# logicboard.net
KiCad netlist of a schematic drawn in EAGLE
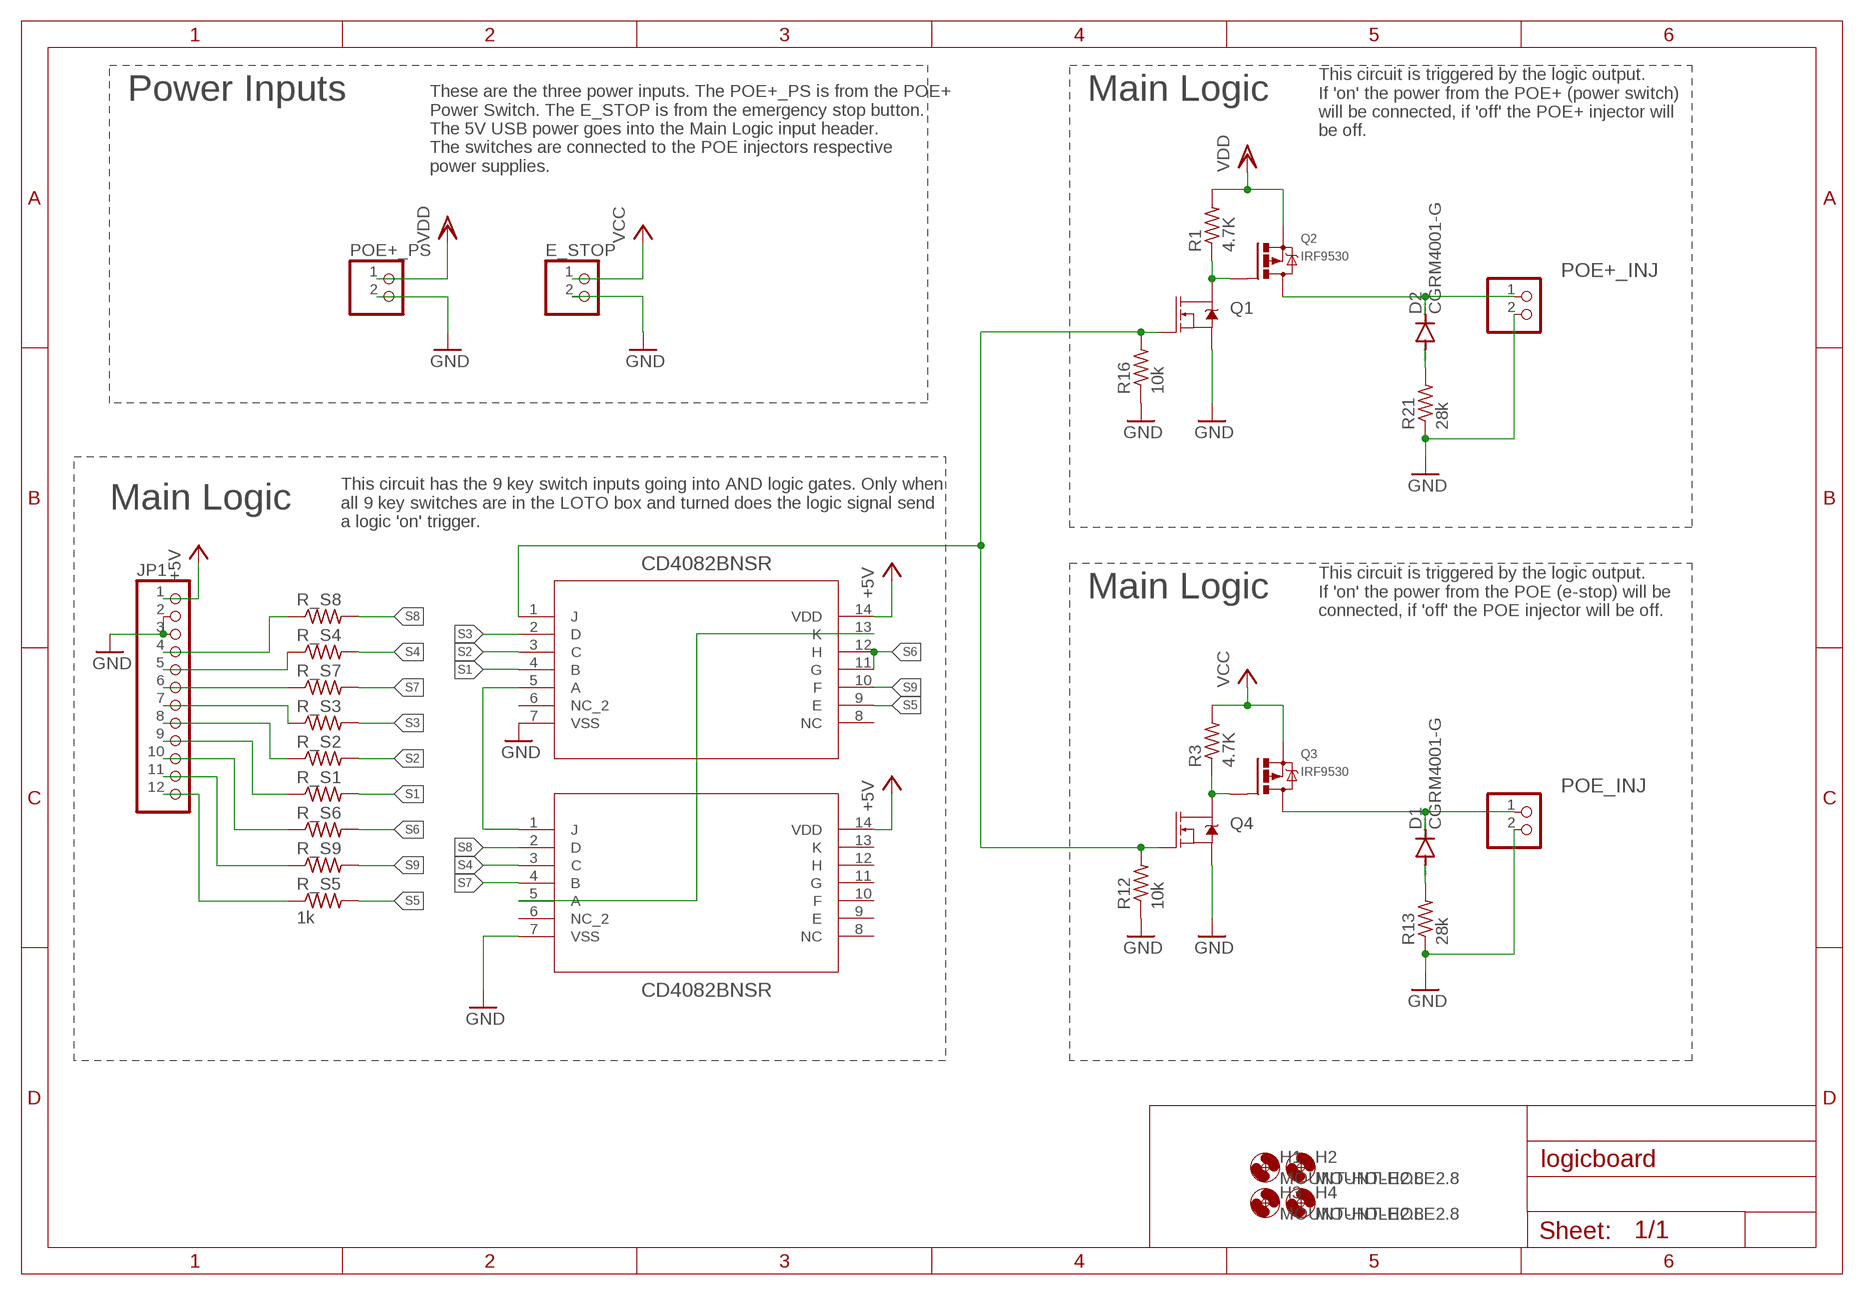
[diagram p0: schematic, sheet 1]

(export (version "E")
  (design (tool "Eeschema 10.0.6"))
  (components
    (comp (ref "D1")
      (value "CGRM4001-G")
      (footprint "eagle-import:SOD-123_MINI-SMA")
      (fields (field (name "MFR") "Central Semiconductor Corp") (field (name "MPN") "CMHSH5-4 TR PBFREE"))
      (libsource (lib "eagle-import") (part "CGRM400-G1"))
    )
    (comp (ref "D2")
      (value "CGRM4001-G")
      (footprint "eagle-import:SOD-123_MINI-SMA")
      (fields (field (name "MFR") "Central Semiconductor Corp") (field (name "MPN") "CMHSH5-4 TR PBFREE"))
      (libsource (lib "eagle-import") (part "CGRM400-G1"))
    )
    (comp (ref "E_STOP")
      (value "PINHD-1X2")
      (footprint "eagle-import:1X02")
      (fields (field (name "MFR") "On Shore Technology Inc.") (field (name "MPN") "OSTVN02A150"))
      (libsource (lib "eagle-import") (part "PINHD-1X2"))
    )
    (comp (ref "H1")
      (value "MOUNT-HOLE2.8")
      (footprint "eagle-import:2,8")
      (libsource (lib "eagle-import") (part "MOUNT-HOLE2.8"))
    )
    (comp (ref "H2")
      (value "MOUNT-HOLE2.8")
      (footprint "eagle-import:2,8")
      (libsource (lib "eagle-import") (part "MOUNT-HOLE2.8"))
    )
    (comp (ref "H3")
      (value "MOUNT-HOLE2.8")
      (footprint "eagle-import:2,8")
      (libsource (lib "eagle-import") (part "MOUNT-HOLE2.8"))
    )
    (comp (ref "H4")
      (value "MOUNT-HOLE2.8")
      (footprint "eagle-import:2,8")
      (libsource (lib "eagle-import") (part "MOUNT-HOLE2.8"))
    )
    (comp (ref "JP1")
      (value "PINHD-1X12")
      (footprint "eagle-import:1X12")
      (fields (field (name "MFR") "TE Connectivity AMP Connectors") (field (name "MPN") "1-640454-2"))
      (libsource (lib "eagle-import") (part "PINHD-1X12"))
    )
    (comp (ref "POE+_INJ")
      (value "PINHD-1X2")
      (footprint "eagle-import:1X02")
      (fields (field (name "MFR") "Molex") (field (name "MPN") "0022232021"))
      (libsource (lib "eagle-import") (part "PINHD-1X2"))
    )
    (comp (ref "POE+_PS")
      (value "PINHD-1X2")
      (footprint "eagle-import:1X02")
      (fields (field (name "MFR") "On Shore Technology Inc.") (field (name "MPN") "OSTVN02A150"))
      (libsource (lib "eagle-import") (part "PINHD-1X2"))
    )
    (comp (ref "POE_INJ")
      (value "PINHD-1X2")
      (footprint "eagle-import:1X02")
      (fields (field (name "MFR") "Molex") (field (name "MPN") "0022232021"))
      (libsource (lib "eagle-import") (part "PINHD-1X2"))
    )
    (comp (ref "Q1")
      (value "220mA/50V/3.5Ω")
      (footprint "eagle-import:SOT23-3")
      (fields (field (name "MFR") "Nexperia USA Inc.") (field (name "MPN") "BSS138P,215"))
      (libsource (lib "eagle-import") (part "MOSFET-NCH-BSS138"))
    )
    (comp (ref "Q2")
      (value "IRF9530")
      (footprint "eagle-import:TO220BV")
      (fields (field (name "MFR") "Infineon Technologies") (field (name "MPN") "IRF9530NPBF"))
      (libsource (lib "eagle-import") (part "IRF9530"))
    )
    (comp (ref "Q3")
      (value "IRF9530")
      (footprint "eagle-import:TO220BV")
      (fields (field (name "MFR") "Infineon Technologies") (field (name "MPN") "IRF9530NPBF"))
      (libsource (lib "eagle-import") (part "IRF9530"))
    )
    (comp (ref "Q4")
      (value "220mA/50V/3.5Ω")
      (footprint "eagle-import:SOT23-3")
      (fields (field (name "MFR") "Nexperia USA Inc.") (field (name "MPN") "BSS138P,215"))
      (libsource (lib "eagle-import") (part "MOSFET-NCH-BSS138"))
    )
    (comp (ref "R1")
      (value "4.7K")
      (footprint "eagle-import:.0805-C-NOSILK")
      (fields (field (name "MFR") "Yageo") (field (name "MPN") "RC0805FR-074K7L"))
      (libsource (lib "eagle-import") (part "R-US_0805-C-NOSILK"))
    )
    (comp (ref "R3")
      (value "4.7K")
      (footprint "eagle-import:.0805-C-NOSILK")
      (fields (field (name "MFR") "Yageo") (field (name "MPN") "RC0805FR-074K7L"))
      (libsource (lib "eagle-import") (part "R-US_0805-C-NOSILK"))
    )
    (comp (ref "R12")
      (value "10k")
      (footprint "eagle-import:.0805-C-NOSILK")
      (fields (field (name "MFR") "Yageo") (field (name "MPN") "RC0805FR-0710KL"))
      (libsource (lib "eagle-import") (part "R-US_0805-C-NOSILK"))
    )
    (comp (ref "R13")
      (value "28k")
      (footprint "eagle-import:.0805-C-NOSILK")
      (fields (field (name "MFR") "Stackpole Electronics Inc") (field (name "MPN") "RMCF0805FT28K0"))
      (libsource (lib "eagle-import") (part "R-US_0805-C-NOSILK"))
    )
    (comp (ref "R16")
      (value "10k")
      (footprint "eagle-import:.0805-C-NOSILK")
      (fields (field (name "MFR") "Yageo") (field (name "MPN") "RC0805FR-0710KL"))
      (libsource (lib "eagle-import") (part "R-US_0805-C-NOSILK"))
    )
    (comp (ref "R21")
      (value "28k")
      (footprint "eagle-import:.0805-C-NOSILK")
      (fields (field (name "MFR") "Stackpole Electronics Inc") (field (name "MPN") "RMCF0805FT28K0"))
      (libsource (lib "eagle-import") (part "R-US_0805-C-NOSILK"))
    )
    (comp (ref "R_S1")
      (value "1k")
      (footprint "eagle-import:.0603-C-NOSILK")
      (fields (field (name "MFR") "Panasonic Electronic Components") (field (name "MPN") "ERJ-PA3F1001V"))
      (libsource (lib "eagle-import") (part "R-US_0603-C-NOSILK"))
    )
    (comp (ref "R_S2")
      (value "1k")
      (footprint "eagle-import:.0603-C-NOSILK")
      (fields (field (name "MFR") "Panasonic Electronic Components") (field (name "MPN") "ERJ-PA3F1001V"))
      (libsource (lib "eagle-import") (part "R-US_0603-C-NOSILK"))
    )
    (comp (ref "R_S3")
      (value "1k")
      (footprint "eagle-import:.0603-C-NOSILK")
      (fields (field (name "MFR") "Panasonic Electronic Components") (field (name "MPN") "ERJ-PA3F1001V"))
      (libsource (lib "eagle-import") (part "R-US_0603-C-NOSILK"))
    )
    (comp (ref "R_S4")
      (value "1k")
      (footprint "eagle-import:.0603-C-NOSILK")
      (fields (field (name "MFR") "Panasonic Electronic Components") (field (name "MPN") "ERJ-PA3F1001V"))
      (libsource (lib "eagle-import") (part "R-US_0603-C-NOSILK"))
    )
    (comp (ref "R_S5")
      (value "1k")
      (footprint "eagle-import:.0603-C-NOSILK")
      (fields (field (name "MFR") "Panasonic Electronic Components") (field (name "MPN") "ERJ-PA3F1001V"))
      (libsource (lib "eagle-import") (part "R-US_0603-C-NOSILK"))
    )
    (comp (ref "R_S6")
      (value "1k")
      (footprint "eagle-import:.0603-C-NOSILK")
      (fields (field (name "MFR") "Panasonic Electronic Components") (field (name "MPN") "ERJ-PA3F1001V"))
      (libsource (lib "eagle-import") (part "R-US_0603-C-NOSILK"))
    )
    (comp (ref "R_S7")
      (value "1k")
      (footprint "eagle-import:.0603-C-NOSILK")
      (fields (field (name "MFR") "Panasonic Electronic Components") (field (name "MPN") "ERJ-PA3F1001V"))
      (libsource (lib "eagle-import") (part "R-US_0603-C-NOSILK"))
    )
    (comp (ref "R_S8")
      (value "1k")
      (footprint "eagle-import:.0603-C-NOSILK")
      (fields (field (name "MFR") "Panasonic Electronic Components") (field (name "MPN") "ERJ-PA3F1001V"))
      (libsource (lib "eagle-import") (part "R-US_0603-C-NOSILK"))
    )
    (comp (ref "R_S9")
      (value "1k")
      (footprint "eagle-import:.0603-C-NOSILK")
      (fields (field (name "MFR") "Panasonic Electronic Components") (field (name "MPN") "ERJ-PA3F1001V"))
      (libsource (lib "eagle-import") (part "R-US_0603-C-NOSILK"))
    )
    (comp (ref "U1")
      (value "CD4082BNSR")
      (footprint "eagle-import:NS14")
      (fields
        (field (name "GENERIC_PART_NUMBER") "CD4082B")
        (field (name "MANUFACTURER") "Texas Instruments")
      )
      (libsource (lib "eagle-import") (part "CD4082BNSR"))
    )
    (comp (ref "U2")
      (value "CD4082BNSR")
      (footprint "eagle-import:NS14")
      (fields
        (field (name "GENERIC_PART_NUMBER") "CD4082B")
        (field (name "MANUFACTURER") "Texas Instruments")
      )
      (libsource (lib "eagle-import") (part "CD4082BNSR"))
    )
  )
  (nets
    (net (code "1") (name "+5V") (class "Default")
      (node (ref "JP1") (pin "1") (pinfunction "1_1") (pintype "passive"))
      (node (ref "U1") (pin "14") (pinfunction "VDD_14") (pintype "power_in"))
      (node (ref "U2") (pin "14") (pinfunction "VDD_14") (pintype "power_in"))
    )
    (net (code "2") (name "GND") (class "Default")
      (node (ref "E_STOP") (pin "2") (pinfunction "2_2") (pintype "passive"))
      (node (ref "JP1") (pin "2") (pinfunction "2_2") (pintype "passive"))
      (node (ref "JP1") (pin "3") (pinfunction "3_3") (pintype "passive"))
      (node (ref "POE+_INJ") (pin "2") (pinfunction "2_2") (pintype "passive"))
      (node (ref "POE+_PS") (pin "2") (pinfunction "2_2") (pintype "passive"))
      (node (ref "POE_INJ") (pin "2") (pinfunction "2_2") (pintype "passive"))
      (node (ref "Q1") (pin "2") (pinfunction "S_2") (pintype "bidirectional"))
      (node (ref "Q4") (pin "2") (pinfunction "S_2") (pintype "bidirectional"))
      (node (ref "R12") (pin "1") (pinfunction "1_1") (pintype "passive"))
      (node (ref "R13") (pin "1") (pinfunction "1_1") (pintype "passive"))
      (node (ref "R16") (pin "1") (pinfunction "1_1") (pintype "passive"))
      (node (ref "R21") (pin "1") (pinfunction "1_1") (pintype "passive"))
      (node (ref "U1") (pin "7") (pinfunction "VSS_7") (pintype "power_in"))
      (node (ref "U2") (pin "7") (pinfunction "VSS_7") (pintype "power_in"))
    )
    (net (code "3") (name "Net-(D1-PadA)") (class "Default")
      (node (ref "D1") (pin "A") (pinfunction "A_A") (pintype "passive"))
      (node (ref "R13") (pin "2") (pinfunction "2_2") (pintype "passive"))
    )
    (net (code "4") (name "Net-(D1-PadC)") (class "Default")
      (node (ref "D1") (pin "C") (pinfunction "C_C") (pintype "passive"))
      (node (ref "POE_INJ") (pin "1") (pinfunction "1_1") (pintype "passive"))
      (node (ref "Q3") (pin "D") (pinfunction "D_D") (pintype "passive"))
    )
    (net (code "5") (name "Net-(D2-PadA)") (class "Default")
      (node (ref "D2") (pin "A") (pinfunction "A_A") (pintype "passive"))
      (node (ref "R21") (pin "2") (pinfunction "2_2") (pintype "passive"))
    )
    (net (code "6") (name "Net-(D2-PadC)") (class "Default")
      (node (ref "D2") (pin "C") (pinfunction "C_C") (pintype "passive"))
      (node (ref "POE+_INJ") (pin "1") (pinfunction "1_1") (pintype "passive"))
      (node (ref "Q2") (pin "D") (pinfunction "D_D") (pintype "passive"))
    )
    (net (code "7") (name "Net-(JP1-Pad4)") (class "Default")
      (node (ref "JP1") (pin "4") (pinfunction "4_4") (pintype "passive"))
      (node (ref "R_S8") (pin "1") (pinfunction "1_1") (pintype "passive"))
    )
    (net (code "8") (name "Net-(JP1-Pad5)") (class "Default")
      (node (ref "JP1") (pin "5") (pinfunction "5_5") (pintype "passive"))
      (node (ref "R_S4") (pin "1") (pinfunction "1_1") (pintype "passive"))
    )
    (net (code "9") (name "Net-(JP1-Pad6)") (class "Default")
      (node (ref "JP1") (pin "6") (pinfunction "6_6") (pintype "passive"))
      (node (ref "R_S7") (pin "1") (pinfunction "1_1") (pintype "passive"))
    )
    (net (code "10") (name "Net-(JP1-Pad7)") (class "Default")
      (node (ref "JP1") (pin "7") (pinfunction "7_7") (pintype "passive"))
      (node (ref "R_S3") (pin "1") (pinfunction "1_1") (pintype "passive"))
    )
    (net (code "11") (name "Net-(JP1-Pad8)") (class "Default")
      (node (ref "JP1") (pin "8") (pinfunction "8_8") (pintype "passive"))
      (node (ref "R_S2") (pin "1") (pinfunction "1_1") (pintype "passive"))
    )
    (net (code "12") (name "Net-(JP1-Pad9)") (class "Default")
      (node (ref "JP1") (pin "9") (pinfunction "9_9") (pintype "passive"))
      (node (ref "R_S1") (pin "1") (pinfunction "1_1") (pintype "passive"))
    )
    (net (code "13") (name "Net-(JP1-Pad10)") (class "Default")
      (node (ref "JP1") (pin "10") (pinfunction "10_10") (pintype "passive"))
      (node (ref "R_S6") (pin "1") (pinfunction "1_1") (pintype "passive"))
    )
    (net (code "14") (name "Net-(JP1-Pad11)") (class "Default")
      (node (ref "JP1") (pin "11") (pinfunction "11_11") (pintype "passive"))
      (node (ref "R_S9") (pin "1") (pinfunction "1_1") (pintype "passive"))
    )
    (net (code "15") (name "Net-(JP1-Pad12)") (class "Default")
      (node (ref "JP1") (pin "12") (pinfunction "12_12") (pintype "passive"))
      (node (ref "R_S5") (pin "1") (pinfunction "1_1") (pintype "passive"))
    )
    (net (code "16") (name "Net-(Q1-D)") (class "Default")
      (node (ref "Q1") (pin "3") (pinfunction "D_3") (pintype "bidirectional"))
      (node (ref "Q2") (pin "G") (pinfunction "G_G") (pintype "passive"))
      (node (ref "R1") (pin "1") (pinfunction "1_1") (pintype "passive"))
    )
    (net (code "17") (name "Net-(Q1-G)") (class "Default")
      (node (ref "Q1") (pin "1") (pinfunction "G_1") (pintype "bidirectional"))
      (node (ref "Q4") (pin "1") (pinfunction "G_1") (pintype "bidirectional"))
      (node (ref "R12") (pin "2") (pinfunction "2_2") (pintype "passive"))
      (node (ref "R16") (pin "2") (pinfunction "2_2") (pintype "passive"))
      (node (ref "U1") (pin "1") (pinfunction "J_1") (pintype "passive"))
    )
    (net (code "18") (name "Net-(Q4-D)") (class "Default")
      (node (ref "Q3") (pin "G") (pinfunction "G_G") (pintype "passive"))
      (node (ref "Q4") (pin "3") (pinfunction "D_3") (pintype "bidirectional"))
      (node (ref "R3") (pin "1") (pinfunction "1_1") (pintype "passive"))
    )
    (net (code "19") (name "Net-(U1-A)") (class "Default")
      (node (ref "U1") (pin "5") (pinfunction "A_5") (pintype "passive"))
      (node (ref "U2") (pin "1") (pinfunction "J_1") (pintype "passive"))
    )
    (net (code "20") (name "Net-(U1-K)") (class "Default")
      (node (ref "U1") (pin "13") (pinfunction "K_13") (pintype "passive"))
      (node (ref "U2") (pin "5") (pinfunction "A_5") (pintype "passive"))
    )
    (net (code "21") (name "S1") (class "Default")
      (node (ref "R_S1") (pin "2") (pinfunction "2_2") (pintype "passive"))
      (node (ref "U1") (pin "4") (pinfunction "B_4") (pintype "passive"))
    )
    (net (code "22") (name "S2") (class "Default")
      (node (ref "R_S2") (pin "2") (pinfunction "2_2") (pintype "passive"))
      (node (ref "U1") (pin "3") (pinfunction "C_3") (pintype "passive"))
    )
    (net (code "23") (name "S3") (class "Default")
      (node (ref "R_S3") (pin "2") (pinfunction "2_2") (pintype "passive"))
      (node (ref "U1") (pin "2") (pinfunction "D_2") (pintype "passive"))
    )
    (net (code "24") (name "S4") (class "Default")
      (node (ref "R_S4") (pin "2") (pinfunction "2_2") (pintype "passive"))
      (node (ref "U2") (pin "3") (pinfunction "C_3") (pintype "passive"))
    )
    (net (code "25") (name "S5") (class "Default")
      (node (ref "R_S5") (pin "2") (pinfunction "2_2") (pintype "passive"))
      (node (ref "U1") (pin "9") (pinfunction "E_9") (pintype "passive"))
    )
    (net (code "26") (name "S6") (class "Default")
      (node (ref "R_S6") (pin "2") (pinfunction "2_2") (pintype "passive"))
      (node (ref "U1") (pin "11") (pinfunction "G_11") (pintype "passive"))
      (node (ref "U1") (pin "12") (pinfunction "H_12") (pintype "passive"))
    )
    (net (code "27") (name "S7") (class "Default")
      (node (ref "R_S7") (pin "2") (pinfunction "2_2") (pintype "passive"))
      (node (ref "U2") (pin "4") (pinfunction "B_4") (pintype "passive"))
    )
    (net (code "28") (name "S8") (class "Default")
      (node (ref "R_S8") (pin "2") (pinfunction "2_2") (pintype "passive"))
      (node (ref "U2") (pin "2") (pinfunction "D_2") (pintype "passive"))
    )
    (net (code "29") (name "S9") (class "Default")
      (node (ref "R_S9") (pin "2") (pinfunction "2_2") (pintype "passive"))
      (node (ref "U1") (pin "10") (pinfunction "F_10") (pintype "passive"))
    )
    (net (code "30") (name "VCC") (class "Default")
      (node (ref "E_STOP") (pin "1") (pinfunction "1_1") (pintype "passive"))
      (node (ref "Q3") (pin "S") (pinfunction "S_S") (pintype "passive"))
      (node (ref "R3") (pin "2") (pinfunction "2_2") (pintype "passive"))
    )
    (net (code "31") (name "VDD") (class "Default")
      (node (ref "POE+_PS") (pin "1") (pinfunction "1_1") (pintype "passive"))
      (node (ref "Q2") (pin "S") (pinfunction "S_S") (pintype "passive"))
      (node (ref "R1") (pin "2") (pinfunction "2_2") (pintype "passive"))
    )
    (net (code "32") (name "unconnected-(U1-NC-Pad8)") (class "Default")
      (node (ref "U1") (pin "8") (pinfunction "NC_8") (pintype "no_connect"))
    )
    (net (code "33") (name "unconnected-(U1-NC_2-Pad6)") (class "Default")
      (node (ref "U1") (pin "6") (pinfunction "NC_2_6") (pintype "no_connect"))
    )
    (net (code "34") (name "unconnected-(U2-E-Pad9)") (class "Default")
      (node (ref "U2") (pin "9") (pinfunction "E_9") (pintype "passive"))
    )
    (net (code "35") (name "unconnected-(U2-F-Pad10)") (class "Default")
      (node (ref "U2") (pin "10") (pinfunction "F_10") (pintype "passive"))
    )
    (net (code "36") (name "unconnected-(U2-G-Pad11)") (class "Default")
      (node (ref "U2") (pin "11") (pinfunction "G_11") (pintype "passive"))
    )
    (net (code "37") (name "unconnected-(U2-H-Pad12)") (class "Default")
      (node (ref "U2") (pin "12") (pinfunction "H_12") (pintype "passive"))
    )
    (net (code "38") (name "unconnected-(U2-K-Pad13)") (class "Default")
      (node (ref "U2") (pin "13") (pinfunction "K_13") (pintype "passive"))
    )
    (net (code "39") (name "unconnected-(U2-NC-Pad8)") (class "Default")
      (node (ref "U2") (pin "8") (pinfunction "NC_8") (pintype "no_connect"))
    )
    (net (code "40") (name "unconnected-(U2-NC_2-Pad6)") (class "Default")
      (node (ref "U2") (pin "6") (pinfunction "NC_2_6") (pintype "no_connect"))
    )
  )
)
